# buck_converter.net
KiCad netlist of a schematic drawn in Altium Designer
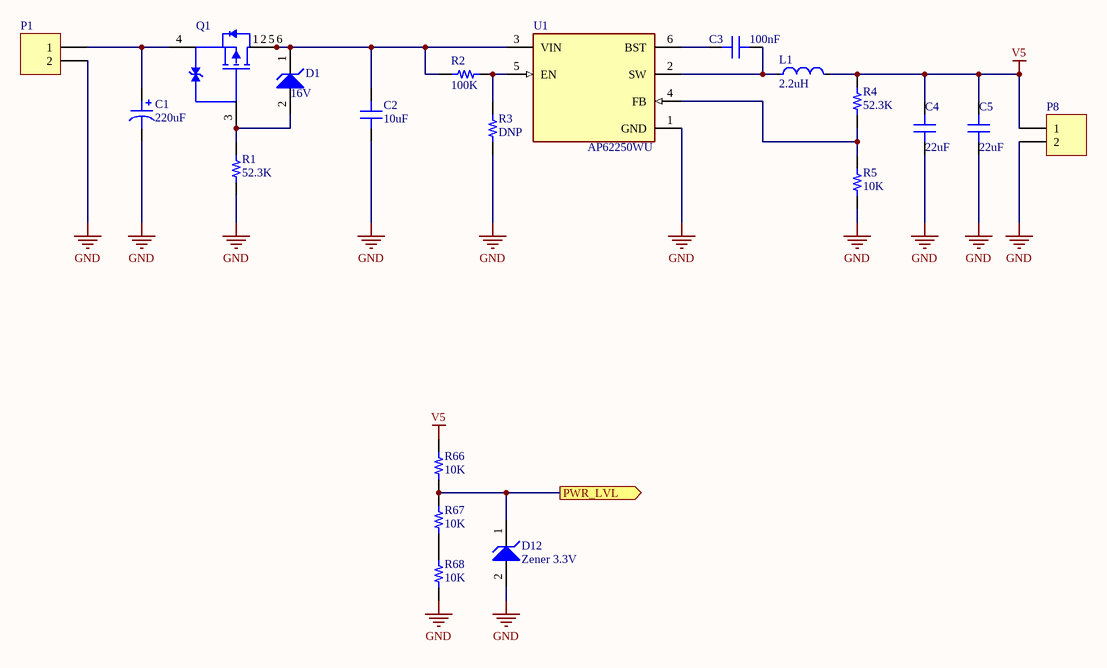
[diagram p0: buck_converter.SchDoc]

(export (version "E")
  (design (tool "Eeschema 10.0.6"))
  (components
    (comp (ref "C1")
      (value "220uF")
      (footprint "CAP TH ALUM ELEC D10.00mm S5.00mm H12.50mm")
      (description "SMT Polarised Capacitor")
      (fields (field (name "MF") "KEMET") (field (name "MP") "ESK227M035AH1AA"))
      (libsource (lib "Capacitor") (part "Polarised Capacitor"))
    )
    (comp (ref "C2")
      (value "10uF")
      (footprint "CAP 0603_1608")
      (description "SMT Capacitor")
      (fields (field (name "MF") "Murata") (field (name "MP") "GRM188R61C106MAALD"))
      (libsource (lib "Capacitor") (part "Capacitor"))
    )
    (comp (ref "C3")
      (value "100nF")
      (footprint "CAP 0603_1608")
      (description "SMT Capacitor")
      (fields (field (name "MF") "TDK") (field (name "MP") "CGA3E2X7R1E104K080AA"))
      (libsource (lib "Capacitor") (part "Capacitor"))
    )
    (comp (ref "C4")
      (value "22uF")
      (footprint "CAP 0603_1608")
      (description "SMT Capacitor")
      (fields (field (name "MF") "Murata") (field (name "MP") "GRM188R61A226ME15D"))
      (libsource (lib "Capacitor") (part "Capacitor"))
    )
    (comp (ref "C5")
      (value "22uF")
      (footprint "CAP 0603_1608")
      (description "SMT Capacitor")
      (fields (field (name "MF") "Murata") (field (name "MP") "GRM188R61A226ME15D"))
      (libsource (lib "Capacitor") (part "Capacitor"))
    )
    (comp (ref "D1")
      (value "16V")
      (footprint "Diodes_SOD-123_0")
      (description "Zener Voltage Regulator")
      (fields (field (name "MANUFACTURER") "On Semiconductor") (field (name "MF") "Onsemi"))
      (libsource (lib "Diode") (part "Zener Diode"))
    )
    (comp (ref "D12")
      (value "Zener 3.3V")
      (footprint "Diodes_SOD-123_0")
      (description "Zener Voltage Regulator")
      (fields (field (name "MANUFACTURER") "On Semiconductor") (field (name "MF") "Onsemi"))
      (libsource (lib "Diode") (part "Zener Diode"))
    )
    (comp (ref "L1")
      (value "2.2uH")
      (footprint "Vishay_IHLP-2020CZ-FP_1_905x2_79-3D_3_0_MFG")
      (description "Fixed Inductors 2.2uH 20% High Temp AEC-Q200")
      (fields (field (name "MF") "Vishay") (field (name "MP") "IHLP2020CZER2R2M11"))
      (libsource (lib "Inductor") (part "Inductor_sm"))
    )
    (comp (ref "P1")
      (value "*")
      (footprint "TEConn_EP2.5_1x2")
      (description "Header, 2-Pin, Right Angle")
      (fields
        (field (name "MF") "TE Connectivity")
        (field (name "MP") "1744426-2")
        (field (name "PUBLISHER") "Altium Limited")
      )
      (libsource (lib "Connector") (part "Header 2H"))
    )
    (comp (ref "P8")
      (value "DNP")
      (footprint "HDR1X2")
      (description "Header, 2-Pin")
      (fields (field (name "PUBLISHER") "Altium Limited"))
      (libsource (lib "Connector") (part "Header 2"))
    )
    (comp (ref "Q1")
      (value "P Mosfet")
      (footprint "Diodes_Inc._TSOT26_MFG")
      (description "P-Channel Enhancement Mode MOS Transistor, 3-Pin SOT23")
      (fields (field (name "MF") "Vishay") (field (name "MP") "SI3421DV-T1-GE3"))
      (libsource (lib "Mosfet") (part "Mosfet-P-6_ESD"))
    )
    (comp (ref "R1")
      (value "52.3K")
      (footprint "RES 0603_1608")
      (description "SMT Resistor")
      (fields (field (name "MF") "YAGEO") (field (name "MP") "AC0603FR-0752K3L"))
      (libsource (lib "Resistor") (part "Resistor"))
    )
    (comp (ref "R2")
      (value "100K")
      (footprint "RES 0603_1608")
      (description "SMT Resistor")
      (fields (field (name "MF") "YAGEO") (field (name "MP") "AC0603FR-07100KL"))
      (libsource (lib "Resistor") (part "Resistor"))
    )
    (comp (ref "R3")
      (value "DNP")
      (footprint "RES 0603_1608")
      (description "SMT Resistor")
      (fields (field (name "MF") "YAGEO") (field (name "MP") "AC0603FR-07100KL"))
      (libsource (lib "Resistor") (part "Resistor"))
    )
    (comp (ref "R4")
      (value "52.3K")
      (footprint "RES 0603_1608")
      (description "SMT Resistor")
      (fields (field (name "MF") "YAGEO") (field (name "MP") "AC0603FR-0752K3L"))
      (libsource (lib "Resistor") (part "Resistor"))
    )
    (comp (ref "R5")
      (value "10K")
      (footprint "RES 0603_1608")
      (description "SMT Resistor")
      (fields (field (name "MF") "YAGEO") (field (name "MP") "AC0603FR-0710KL"))
      (libsource (lib "Resistor") (part "Resistor"))
    )
    (comp (ref "R66")
      (value "10K")
      (footprint "RES 0603_1608")
      (description "SMT Resistor")
      (fields (field (name "MF") "YAGEO") (field (name "MP") "AC0603FR-0710KL"))
      (libsource (lib "Resistor") (part "Resistor"))
    )
    (comp (ref "R67")
      (value "10K")
      (footprint "RES 0603_1608")
      (description "SMT Resistor")
      (fields (field (name "MF") "YAGEO") (field (name "MP") "AC0603FR-0710KL"))
      (libsource (lib "Resistor") (part "Resistor"))
    )
    (comp (ref "R68")
      (value "10K")
      (footprint "RES 0603_1608")
      (description "SMT Resistor")
      (fields (field (name "MF") "YAGEO") (field (name "MP") "AC0603FR-0710KL"))
      (libsource (lib "Resistor") (part "Resistor"))
    )
    (comp (ref "U1")
      (value "AP62250WU")
      (footprint "Diodes_Inc._TSOT26_MFG")
      (description "Switching Voltage Regulators DCDC Conv HV Buck TSOT26")
      (fields (field (name "MF") "Diodes Incorporated") (field (name "MP") "AP62250WU-7"))
      (libsource (lib "SwitchingRegulators") (part "AP62250WU"))
    )
  )
  (nets
    (net (code "1") (name "/PWR_LVL") (class "Default")
      (node (ref "D12") (pin "1") (pinfunction "K_1") (pintype "passive"))
      (node (ref "R66") (pin "2") (pinfunction "2_2") (pintype "passive"))
      (node (ref "R67") (pin "1") (pinfunction "1_1") (pintype "passive"))
    )
    (net (code "2") (name "GND") (class "Default")
      (node (ref "C1") (pin "2") (pinfunction "2_2") (pintype "passive"))
      (node (ref "C2") (pin "2") (pinfunction "2_2") (pintype "passive"))
      (node (ref "C4") (pin "2") (pinfunction "2_2") (pintype "passive"))
      (node (ref "C5") (pin "2") (pinfunction "2_2") (pintype "passive"))
      (node (ref "D12") (pin "2") (pinfunction "A_2") (pintype "passive"))
      (node (ref "P1") (pin "2") (pinfunction "2_2") (pintype "passive"))
      (node (ref "P8") (pin "2") (pinfunction "2_2") (pintype "passive"))
      (node (ref "R1") (pin "2") (pinfunction "2_2") (pintype "passive"))
      (node (ref "R3") (pin "2") (pinfunction "2_2") (pintype "passive"))
      (node (ref "R5") (pin "2") (pinfunction "2_2") (pintype "passive"))
      (node (ref "R68") (pin "2") (pinfunction "2_2") (pintype "passive"))
      (node (ref "U1") (pin "1") (pinfunction "GND_1") (pintype "power_in"))
    )
    (net (code "3") (name "Net-(D1-A)") (class "Default")
      (node (ref "D1") (pin "2") (pinfunction "A_2") (pintype "passive"))
      (node (ref "Q1") (pin "3") (pinfunction "G_3") (pintype "passive"))
      (node (ref "R1") (pin "1") (pinfunction "1_1") (pintype "passive"))
    )
    (net (code "4") (name "Net-(D1-K)") (class "Default")
      (node (ref "C2") (pin "1") (pinfunction "1_1") (pintype "passive"))
      (node (ref "D1") (pin "1") (pinfunction "K_1") (pintype "passive"))
      (node (ref "Q1") (pin "1") (pinfunction "D_1") (pintype "passive"))
      (node (ref "Q1") (pin "2") (pinfunction "D_2") (pintype "passive"))
      (node (ref "Q1") (pin "5") (pinfunction "D_5") (pintype "passive"))
      (node (ref "Q1") (pin "6") (pinfunction "D_6") (pintype "passive"))
      (node (ref "R2") (pin "2") (pinfunction "2_2") (pintype "passive"))
      (node (ref "U1") (pin "3") (pinfunction "VIN_3") (pintype "power_in"))
    )
    (net (code "5") (name "Net-(Q1-S)") (class "Default")
      (node (ref "C1") (pin "1") (pinfunction "1_1") (pintype "passive"))
      (node (ref "P1") (pin "1") (pinfunction "1_1") (pintype "passive"))
      (node (ref "Q1") (pin "4") (pinfunction "S_4") (pintype "passive"))
    )
    (net (code "6") (name "Net-(R67-Pad2)") (class "Default")
      (node (ref "R67") (pin "2") (pinfunction "2_2") (pintype "passive"))
      (node (ref "R68") (pin "1") (pinfunction "1_1") (pintype "passive"))
    )
    (net (code "7") (name "Net-(U1-BST)") (class "Default")
      (node (ref "C3") (pin "1") (pinfunction "1_1") (pintype "passive"))
      (node (ref "U1") (pin "6") (pinfunction "BST_6") (pintype "passive"))
    )
    (net (code "8") (name "Net-(U1-EN)") (class "Default")
      (node (ref "R2") (pin "1") (pinfunction "1_1") (pintype "passive"))
      (node (ref "R3") (pin "1") (pinfunction "1_1") (pintype "passive"))
      (node (ref "U1") (pin "5") (pinfunction "EN_5") (pintype "input"))
    )
    (net (code "9") (name "Net-(U1-FB)") (class "Default")
      (node (ref "R4") (pin "2") (pinfunction "2_2") (pintype "passive"))
      (node (ref "R5") (pin "1") (pinfunction "1_1") (pintype "passive"))
      (node (ref "U1") (pin "4") (pinfunction "FB_4") (pintype "input"))
    )
    (net (code "10") (name "Net-(U1-SW)") (class "Default")
      (node (ref "C3") (pin "2") (pinfunction "2_2") (pintype "passive"))
      (node (ref "L1") (pin "1") (pinfunction "1_1") (pintype "passive"))
      (node (ref "U1") (pin "2") (pinfunction "SW_2") (pintype "passive"))
    )
    (net (code "11") (name "V5") (class "Default")
      (node (ref "C4") (pin "1") (pinfunction "1_1") (pintype "passive"))
      (node (ref "C5") (pin "1") (pinfunction "1_1") (pintype "passive"))
      (node (ref "L1") (pin "2") (pinfunction "2_2") (pintype "passive"))
      (node (ref "P8") (pin "1") (pinfunction "1_1") (pintype "passive"))
      (node (ref "R4") (pin "1") (pinfunction "1_1") (pintype "passive"))
      (node (ref "R66") (pin "1") (pinfunction "1_1") (pintype "passive"))
    )
  )
)
